# Sheet2.net
KiCad netlist of a schematic drawn in Altium Designer
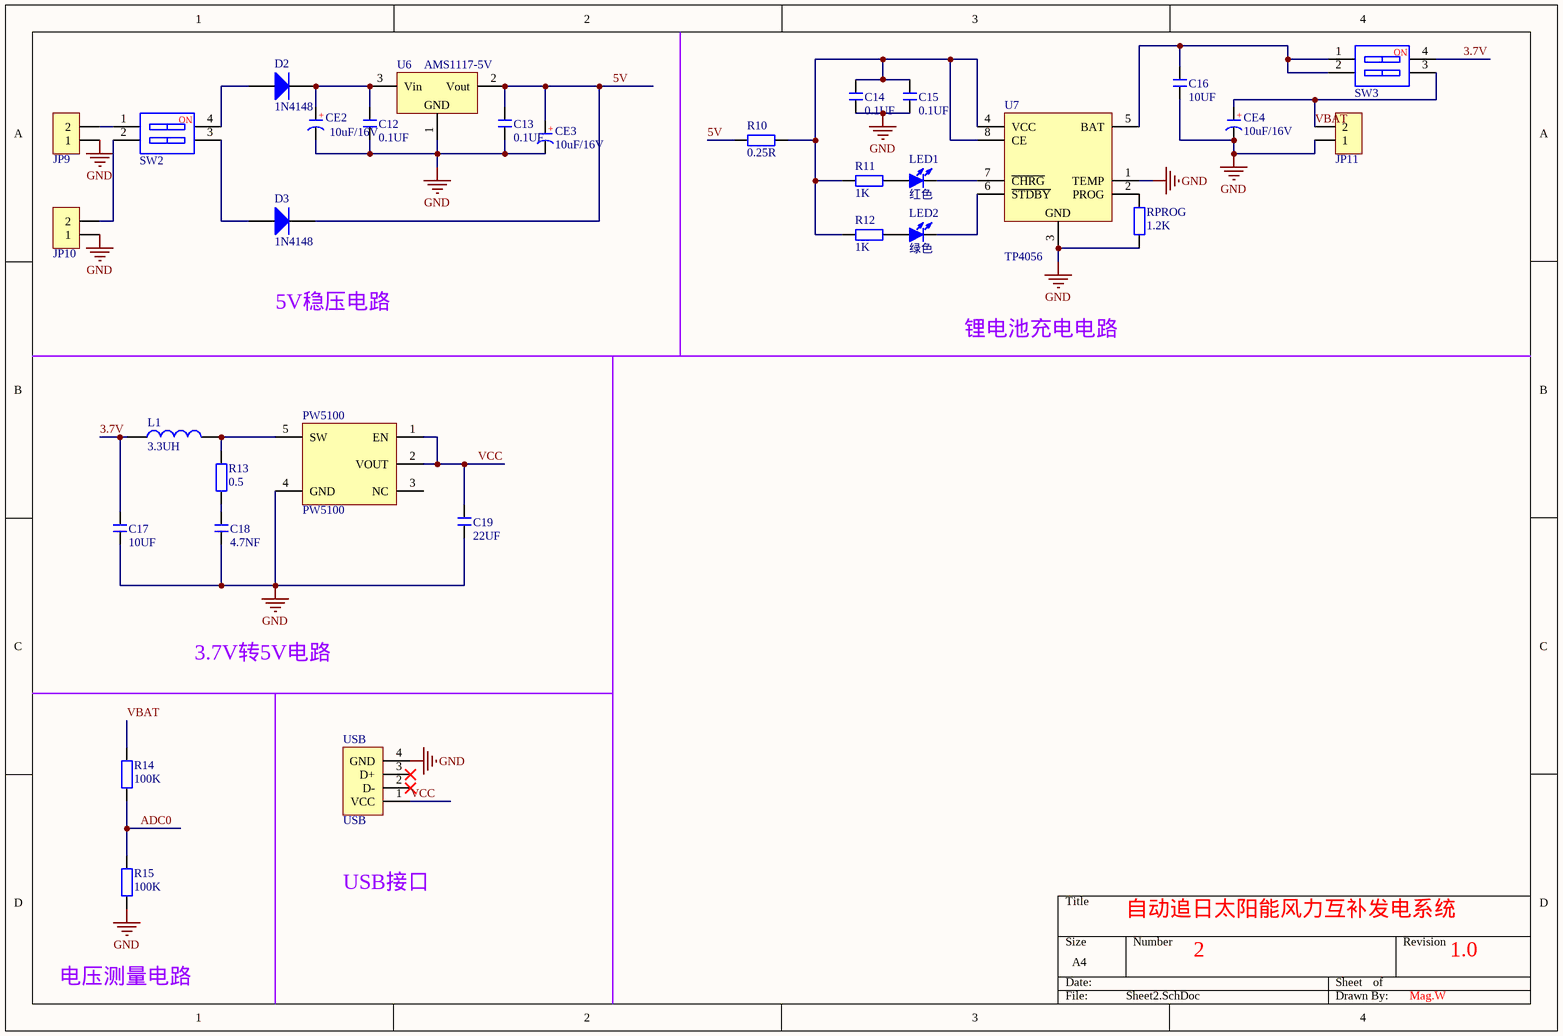
[diagram p0: Sheet2.SchDoc]

(export (version "E")
  (design (tool "Eeschema 10.0.6"))
  (components
    (comp (ref "C12")
      (value "0.1UF")
      (footprint "C 0805_L")
      (description "贴片电容")
      (libsource (lib "0.1 - 电阻-电容-电感") (part "C"))
    )
    (comp (ref "C13")
      (value "0.1UF")
      (footprint "C 0805_L")
      (description "贴片电容")
      (libsource (lib "0.1 - 电阻-电容-电感") (part "C"))
    )
    (comp (ref "C14")
      (value "0.1UF")
      (footprint "C 0805_L")
      (description "贴片电容")
      (libsource (lib "0.1 - 电阻-电容-电感") (part "C"))
    )
    (comp (ref "C15")
      (value "0.1UF")
      (footprint "C 0805_L")
      (description "贴片电容")
      (libsource (lib "0.1 - 电阻-电容-电感") (part "C"))
    )
    (comp (ref "C16")
      (value "10UF")
      (footprint "C 0805_L")
      (description "贴片电容")
      (libsource (lib "0.1 - 电阻-电容-电感") (part "C"))
    )
    (comp (ref "C17")
      (value "10UF")
      (footprint "C 0805_L")
      (description "贴片电容")
      (libsource (lib "0.1 - 电阻-电容-电感") (part "C"))
    )
    (comp (ref "C18")
      (value "4.7NF")
      (footprint "C 0805_L")
      (description "贴片电容")
      (libsource (lib "0.1 - 电阻-电容-电感") (part "C"))
    )
    (comp (ref "C19")
      (value "22UF")
      (footprint "C 0805_L")
      (description "贴片电容")
      (libsource (lib "0.1 - 电阻-电容-电感") (part "C"))
    )
    (comp (ref "CE2")
      (value "10uF/16V")
      (footprint "CAP 1.5*4*8 - BK")
      (description "直插电解电容")
      (libsource (lib "0.1 - 电阻-电容-电感") (part "CE"))
    )
    (comp (ref "CE3")
      (value "10uF/16V")
      (footprint "CAP 1.5*4*8 - BK")
      (description "直插电解电容")
      (libsource (lib "0.1 - 电阻-电容-电感") (part "CE"))
    )
    (comp (ref "CE4")
      (value "10uF/16V")
      (footprint "CAP 1.5*4*8 - BK")
      (description "直插电解电容")
      (libsource (lib "0.1 - 电阻-电容-电感") (part "CE"))
    )
    (comp (ref "D2")
      (value "Diode")
      (footprint "DIODE-1206")
      (description "二极管")
      (fields (field (name "TYPE") "1N4148") (field (name "PUBLISHER") "Altium Limited"))
      (libsource (lib "0.2 - 二极管-整流桥") (part "Diode"))
    )
    (comp (ref "D3")
      (value "Diode")
      (footprint "DIODE-1206")
      (description "二极管")
      (fields (field (name "TYPE") "1N4148") (field (name "PUBLISHER") "Altium Limited"))
      (libsource (lib "0.2 - 二极管-整流桥") (part "Diode"))
    )
    (comp (ref "JP9")
      (value "HDR-1X2")
      (footprint "KF350-2P")
      (description "2P接插件")
      (fields (field (name "版权归属") "封装库来自淘宝卖家 ID：黄晶宝石"))
      (libsource (lib "5.5 - 接插件-脚距3.5") (part "Header 2"))
    )
    (comp (ref "JP10")
      (value "HDR-1X2")
      (footprint "KF350-2P")
      (description "2P接插件")
      (fields (field (name "版权归属") "封装库来自淘宝卖家 ID：黄晶宝石"))
      (libsource (lib "5.5 - 接插件-脚距3.5") (part "Header 2"))
    )
    (comp (ref "JP11")
      (value "HDR-1X2")
      (footprint "XH2.54-WI-2P")
      (description "2P接插件")
      (fields (field (name "版权归属") "封装库来自淘宝 ID：黄晶宝石"))
      (libsource (lib "5.4 - 接插件-脚距2.54 (100mil) ") (part "Header 2"))
    )
    (comp (ref "L1")
      (value "3.3UH")
      (footprint "L 0805")
      (description "小功率贴片电感")
      (libsource (lib "0.1 - 电阻-电容-电感") (part "L"))
    )
    (comp (ref "LED1")
      (value "红色")
      (footprint "LED 0603R")
      (description "贴片LED")
      (fields (field (name "版权归属") "封装库来自淘宝 ID：黄晶宝石"))
      (libsource (lib "0.3 - LED发光二极管") (part "LED-SMD"))
    )
    (comp (ref "LED2")
      (value "绿色")
      (footprint "LED 0603G")
      (description "贴片LED")
      (fields (field (name "版权归属") "封装库来自淘宝 ID：黄晶宝石"))
      (libsource (lib "0.3 - LED发光二极管") (part "LED-SMD"))
    )
    (comp (ref "PW5100")
      (value "PW5100")
      (footprint "PCBComponent_1")
      (libsource (lib "PW5100") (part "PW5100"))
    )
    (comp (ref "R10")
      (value "0.25R")
      (footprint "R 0805_L")
      (description "贴片电阻")
      (fields (field (name "版权归属") "来自淘宝 ID：黄晶宝石"))
      (libsource (lib "0.1 - 电阻-电容-电感") (part "R"))
    )
    (comp (ref "R11")
      (value "1K")
      (footprint "R 0805_L")
      (description "贴片电阻")
      (fields (field (name "版权归属") "来自淘宝 ID：黄晶宝石"))
      (libsource (lib "0.1 - 电阻-电容-电感") (part "R"))
    )
    (comp (ref "R12")
      (value "1K")
      (footprint "R 0805_L")
      (description "贴片电阻")
      (fields (field (name "版权归属") "来自淘宝 ID：黄晶宝石"))
      (libsource (lib "0.1 - 电阻-电容-电感") (part "R"))
    )
    (comp (ref "R13")
      (value "0.5")
      (footprint "R 0805_L")
      (description "贴片电阻")
      (fields (field (name "版权归属") "来自淘宝 ID：黄晶宝石"))
      (libsource (lib "0.1 - 电阻-电容-电感") (part "R"))
    )
    (comp (ref "R14")
      (value "100K")
      (footprint "R 0805_L")
      (description "贴片电阻")
      (fields (field (name "版权归属") "来自淘宝 ID：黄晶宝石"))
      (libsource (lib "0.1 - 电阻-电容-电感") (part "R"))
    )
    (comp (ref "R15")
      (value "100K")
      (footprint "R 0805_L")
      (description "贴片电阻")
      (fields (field (name "版权归属") "来自淘宝 ID：黄晶宝石"))
      (libsource (lib "0.1 - 电阻-电容-电感") (part "R"))
    )
    (comp (ref "RPROG")
      (value "1.2K")
      (footprint "R 0805_L")
      (description "贴片电阻")
      (fields (field (name "版权归属") "来自淘宝 ID：黄晶宝石"))
      (libsource (lib "0.1 - 电阻-电容-电感") (part "R"))
    )
    (comp (ref "SW2")
      (value "SW-2P")
      (footprint "CSW DIP-2P")
      (description "2路编码开关")
      (libsource (lib "0.7 - 常用按键-开关") (part "SW-2P"))
    )
    (comp (ref "SW3")
      (value "SW-2P")
      (footprint "CSW DIP-2P")
      (description "2路编码开关")
      (libsource (lib "0.7 - 常用按键-开关") (part "SW-2P"))
    )
    (comp (ref "U6")
      (value "AMS1117-5V")
      (footprint "SOT223_L")
      (description "三端稳压芯片")
      (libsource (lib "1.1 - 电源类芯片") (part "AMS1117"))
    )
    (comp (ref "U7")
      (value "TP4056")
      (footprint "SO8")
      (description "锂电池充电管理")
      (libsource (lib "1.0 - 常见芯片") (part "TP4056"))
    )
    (comp (ref "USB")
      (value "USB")
      (footprint "USB-A/S_A")
      (description "USB-A型母接口")
      (fields (field (name "版权归属") "封装库来自淘宝 ID：黄晶宝石"))
      (libsource (lib "0.8 - 以太网-音频-USB插座") (part "USB-A/S"))
    )
  )
  (nets
    (net (code "1") (name "/3.7V") (class "Default")
      (node (ref "C17") (pin "2") (pinfunction "2_2") (pintype "passive"))
      (node (ref "L1") (pin "1") (pinfunction "1_1") (pintype "passive"))
      (node (ref "SW3") (pin "4") (pinfunction "4_4") (pintype "passive"))
    )
    (net (code "2") (name "/5V") (class "Default")
      (node (ref "C13") (pin "1") (pinfunction "1_1") (pintype "passive"))
      (node (ref "CE3") (pin "1") (pinfunction "A_1") (pintype "passive"))
      (node (ref "D3") (pin "2") (pinfunction "K_2") (pintype "passive"))
      (node (ref "R10") (pin "1") (pinfunction "1_1") (pintype "passive"))
      (node (ref "U6") (pin "2") (pinfunction "Vout_2") (pintype "passive"))
    )
    (net (code "3") (name "/ADC0") (class "Default")
      (node (ref "R14") (pin "1") (pinfunction "1_1") (pintype "passive"))
      (node (ref "R15") (pin "2") (pinfunction "2_2") (pintype "passive"))
    )
    (net (code "4") (name "/VBAT") (class "Default")
      (node (ref "CE4") (pin "1") (pinfunction "A_1") (pintype "passive"))
      (node (ref "JP11") (pin "2") (pinfunction "2_2") (pintype "passive"))
      (node (ref "R14") (pin "2") (pinfunction "2_2") (pintype "passive"))
      (node (ref "SW3") (pin "3") (pinfunction "3_3") (pintype "passive"))
    )
    (net (code "5") (name "/VCC") (class "Default")
      (node (ref "C19") (pin "2") (pinfunction "2_2") (pintype "passive"))
      (node (ref "PW5100") (pin "1") (pinfunction "EN_1") (pintype "passive"))
      (node (ref "PW5100") (pin "2") (pinfunction "VOUT_2") (pintype "passive"))
      (node (ref "USB") (pin "1") (pinfunction "VCC_1") (pintype "passive"))
    )
    (net (code "6") (name "GND") (class "Default")
      (node (ref "C12") (pin "2") (pinfunction "2_2") (pintype "passive"))
      (node (ref "C13") (pin "2") (pinfunction "2_2") (pintype "passive"))
      (node (ref "C14") (pin "1") (pinfunction "1_1") (pintype "passive"))
      (node (ref "C15") (pin "1") (pinfunction "1_1") (pintype "passive"))
      (node (ref "C16") (pin "1") (pinfunction "1_1") (pintype "passive"))
      (node (ref "C17") (pin "1") (pinfunction "1_1") (pintype "passive"))
      (node (ref "C18") (pin "1") (pinfunction "1_1") (pintype "passive"))
      (node (ref "C19") (pin "1") (pinfunction "1_1") (pintype "passive"))
      (node (ref "CE2") (pin "2") (pinfunction "K_2") (pintype "passive"))
      (node (ref "CE3") (pin "2") (pinfunction "K_2") (pintype "passive"))
      (node (ref "CE4") (pin "2") (pinfunction "K_2") (pintype "passive"))
      (node (ref "JP10") (pin "1") (pinfunction "1_1") (pintype "passive"))
      (node (ref "JP11") (pin "1") (pinfunction "1_1") (pintype "passive"))
      (node (ref "JP9") (pin "1") (pinfunction "1_1") (pintype "passive"))
      (node (ref "PW5100") (pin "4") (pinfunction "GND_4") (pintype "passive"))
      (node (ref "R15") (pin "1") (pinfunction "1_1") (pintype "passive"))
      (node (ref "RPROG") (pin "1") (pinfunction "1_1") (pintype "passive"))
      (node (ref "U6") (pin "1") (pinfunction "GND_1") (pintype "passive"))
      (node (ref "U7") (pin "1") (pinfunction "TEMP_1") (pintype "passive"))
      (node (ref "U7") (pin "3") (pinfunction "GND_3") (pintype "passive"))
      (node (ref "USB") (pin "4") (pinfunction "GND_4") (pintype "passive"))
    )
    (net (code "7") (name "Net-(C18-Pad2)") (class "Default")
      (node (ref "C18") (pin "2") (pinfunction "2_2") (pintype "passive"))
      (node (ref "R13") (pin "2") (pinfunction "2_2") (pintype "passive"))
    )
    (net (code "8") (name "Net-(CE2-A)") (class "Default")
      (node (ref "C12") (pin "1") (pinfunction "1_1") (pintype "passive"))
      (node (ref "CE2") (pin "1") (pinfunction "A_1") (pintype "passive"))
      (node (ref "D2") (pin "2") (pinfunction "K_2") (pintype "passive"))
      (node (ref "U6") (pin "3") (pinfunction "Vin_3") (pintype "passive"))
    )
    (net (code "9") (name "Net-(D2-A)") (class "Default")
      (node (ref "D2") (pin "1") (pinfunction "A_1") (pintype "passive"))
      (node (ref "SW2") (pin "4") (pinfunction "4_4") (pintype "passive"))
    )
    (net (code "10") (name "Net-(D3-A)") (class "Default")
      (node (ref "D3") (pin "1") (pinfunction "A_1") (pintype "passive"))
      (node (ref "SW2") (pin "3") (pinfunction "3_3") (pintype "passive"))
    )
    (net (code "11") (name "Net-(JP9-Pad2)") (class "Default")
      (node (ref "JP9") (pin "2") (pinfunction "2_2") (pintype "passive"))
      (node (ref "SW2") (pin "1") (pinfunction "1_1") (pintype "passive"))
    )
    (net (code "12") (name "Net-(JP10-Pad2)") (class "Default")
      (node (ref "JP10") (pin "2") (pinfunction "2_2") (pintype "passive"))
      (node (ref "SW2") (pin "2") (pinfunction "2_2") (pintype "passive"))
    )
    (net (code "13") (name "Net-(LED1-A)") (class "Default")
      (node (ref "LED1") (pin "1") (pinfunction "A_1") (pintype "passive"))
      (node (ref "R11") (pin "2") (pinfunction "2_2") (pintype "passive"))
    )
    (net (code "14") (name "Net-(LED1-K)") (class "Default")
      (node (ref "LED1") (pin "2") (pinfunction "K_2") (pintype "passive"))
      (node (ref "U7") (pin "7") (pinfunction "~{CHRG}_7") (pintype "passive"))
    )
    (net (code "15") (name "Net-(LED2-A)") (class "Default")
      (node (ref "LED2") (pin "1") (pinfunction "A_1") (pintype "passive"))
      (node (ref "R12") (pin "2") (pinfunction "2_2") (pintype "passive"))
    )
    (net (code "16") (name "Net-(LED2-K)") (class "Default")
      (node (ref "LED2") (pin "2") (pinfunction "K_2") (pintype "passive"))
      (node (ref "U7") (pin "6") (pinfunction "~{STDBY}_6") (pintype "passive"))
    )
    (net (code "17") (name "Net-(PW5100-SW)") (class "Default")
      (node (ref "L1") (pin "2") (pinfunction "2_2") (pintype "passive"))
      (node (ref "PW5100") (pin "5") (pinfunction "SW_5") (pintype "passive"))
      (node (ref "R13") (pin "1") (pinfunction "1_1") (pintype "passive"))
    )
    (net (code "18") (name "Net-(U7-BAT)") (class "Default")
      (node (ref "C16") (pin "2") (pinfunction "2_2") (pintype "passive"))
      (node (ref "SW3") (pin "1") (pinfunction "1_1") (pintype "passive"))
      (node (ref "SW3") (pin "2") (pinfunction "2_2") (pintype "passive"))
      (node (ref "U7") (pin "5") (pinfunction "BAT_5") (pintype "passive"))
    )
    (net (code "19") (name "Net-(U7-CE)") (class "Default")
      (node (ref "C14") (pin "2") (pinfunction "2_2") (pintype "passive"))
      (node (ref "C15") (pin "2") (pinfunction "2_2") (pintype "passive"))
      (node (ref "R10") (pin "2") (pinfunction "2_2") (pintype "passive"))
      (node (ref "R11") (pin "1") (pinfunction "1_1") (pintype "passive"))
      (node (ref "R12") (pin "1") (pinfunction "1_1") (pintype "passive"))
      (node (ref "U7") (pin "4") (pinfunction "VCC_4") (pintype "passive"))
      (node (ref "U7") (pin "8") (pinfunction "CE_8") (pintype "passive"))
    )
    (net (code "20") (name "Net-(U7-PROG)") (class "Default")
      (node (ref "RPROG") (pin "2") (pinfunction "2_2") (pintype "passive"))
      (node (ref "U7") (pin "2") (pinfunction "PROG_2") (pintype "passive"))
    )
    (net (code "21") (name "unconnected-(PW5100-NC-Pad3)") (class "Default")
      (node (ref "PW5100") (pin "3") (pinfunction "NC_3") (pintype "passive"))
    )
    (net (code "22") (name "unconnected-(USB-D+-Pad3)") (class "Default")
      (node (ref "USB") (pin "3") (pinfunction "D+_3") (pintype "passive+no_connect"))
    )
    (net (code "23") (name "unconnected-(USB-D--Pad2)") (class "Default")
      (node (ref "USB") (pin "2") (pinfunction "D-_2") (pintype "passive+no_connect"))
    )
  )
)
